# step_down.net
KiCad netlist of a schematic drawn in EAGLE
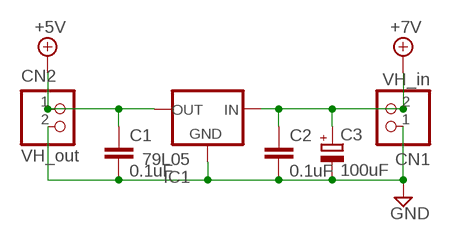
[diagram p0: schematic, sheet 1]

(export (version "E")
  (design (tool "Eeschema 10.0.6"))
  (components
    (comp (ref "C1")
      (value "0.1uF")
      (footprint "eagle-import:C050-025X075")
      (libsource (lib "eagle-import") (part "C-EU050-025X075"))
    )
    (comp (ref "C2")
      (value "0.1uF")
      (footprint "eagle-import:C050-025X075")
      (libsource (lib "eagle-import") (part "C-EU050-025X075"))
    )
    (comp (ref "C3")
      (value "100uF")
      (footprint "eagle-import:E2-5")
      (libsource (lib "eagle-import") (part "CPOL-EUE2-5"))
    )
    (comp (ref "CN1")
      (value "VH_in")
      (footprint "eagle-import:B2P-VH")
      (libsource (lib "eagle-import") (part "B2P-VH"))
    )
    (comp (ref "CN2")
      (value "VH_out")
      (footprint "eagle-import:B2P-VH")
      (libsource (lib "eagle-import") (part "B2P-VH"))
    )
    (comp (ref "IC1")
      (value "79L05")
      (footprint "eagle-import:79LXX")
      (libsource (lib "eagle-import") (part "79LXX"))
    )
  )
  (nets
    (net (code "1") (name "+5V") (class "Default")
      (node (ref "C1") (pin "1") (pinfunction "1_1") (pintype "passive"))
      (node (ref "CN2") (pin "1") (pinfunction "1_1") (pintype "passive"))
      (node (ref "IC1") (pin "OUT") (pinfunction "OUT_OUT") (pintype "passive"))
    )
    (net (code "2") (name "+7V") (class "Default")
      (node (ref "C2") (pin "1") (pinfunction "1_1") (pintype "passive"))
      (node (ref "C3") (pin "+") (pinfunction "+_+") (pintype "passive"))
      (node (ref "CN1") (pin "2") (pinfunction "2_2") (pintype "passive"))
      (node (ref "IC1") (pin "IN") (pinfunction "IN_IN") (pintype "input"))
    )
    (net (code "3") (name "GND") (class "Default")
      (node (ref "C1") (pin "2") (pinfunction "2_2") (pintype "passive"))
      (node (ref "C2") (pin "2") (pinfunction "2_2") (pintype "passive"))
      (node (ref "C3") (pin "-") (pinfunction "-_-") (pintype "passive"))
      (node (ref "CN1") (pin "1") (pinfunction "1_1") (pintype "passive"))
      (node (ref "CN2") (pin "2") (pinfunction "2_2") (pintype "passive"))
      (node (ref "IC1") (pin "GND") (pinfunction "GND_GND") (pintype "input"))
    )
  )
)
